# PhotodiodeDaughterBoard.net
KiCad netlist of a schematic drawn in Altium Designer
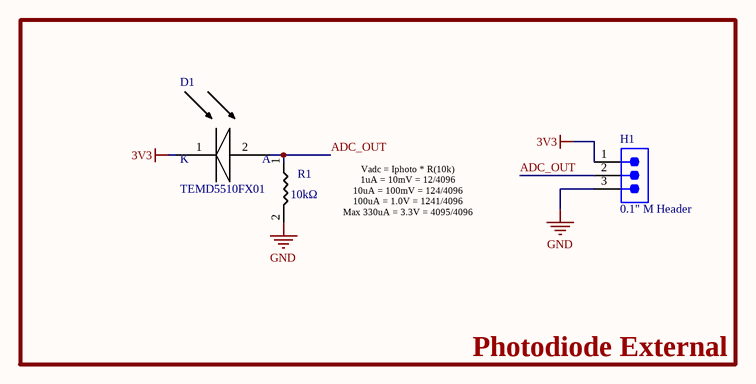
[diagram p0: PhotodiodeDaughterBoard.SchDoc]

(export (version "E")
  (design (tool "Eeschema 10.0.6"))
  (components
    (comp (ref "D1")
      (value "TEMD5510FX01")
      (footprint "TEMD5510FX01")
      (description "Ambient Light Sensor Photodiode")
      (fields (field (name "DIGIKEY PART NUMBER") "TEMD5510FX01CT-ND"))
      (libsource (lib "SunflowerSCH") (part "TEMD5510FX01"))
    )
    (comp (ref "H1")
      (value "0.1\" M Header")
      (footprint "3_PIN_100mil_Photodiode")
      (description "CONN HEADER VERT 3POS 2.54MM")
      (fields
        (field (name "MANUFACTURER") "Sullins")
        (field (name "MANUFACTURER PART NUMBER") "PRPC003SAAN-RC")
      )
      (libsource (lib "SunflowerSCH") (part "Photodiode_3Pin_100mil"))
    )
    (comp (ref "R1")
      (value "10kΩ")
      (footprint "0603_Resistor")
      (description "Fixed Resistor, Metal Glaze/Thick Film, 0.1W, 10000ohm, 75V, 1% +/-Tol, Surface Mount, 0603")
      (fields
        (field (name "MANUFACTURER") "Vishay")
        (field (name "MANUFACTURER PART NUMBER") "CRCW060310K0FKEA")
      )
      (libsource (lib "SunflowerSCH") (part "R_0603_Photodiode"))
    )
  )
  (nets
    (net (code "1") (name "/ADC_OUT") (class "Default")
      (node (ref "D1") (pin "2") (pinfunction "A_2") (pintype "passive"))
      (node (ref "H1") (pin "2") (pinfunction "2_2") (pintype "passive"))
      (node (ref "R1") (pin "1") (pinfunction "1_1") (pintype "passive"))
    )
    (net (code "2") (name "3V3") (class "Default")
      (node (ref "D1") (pin "1") (pinfunction "K_1") (pintype "passive"))
      (node (ref "H1") (pin "1") (pinfunction "1_1") (pintype "passive"))
    )
    (net (code "3") (name "GND") (class "Default")
      (node (ref "H1") (pin "3") (pinfunction "3_3") (pintype "passive"))
      (node (ref "R1") (pin "2") (pinfunction "2_2") (pintype "passive"))
    )
  )
)
